# main.net
KiCad netlist of a schematic drawn in EAGLE
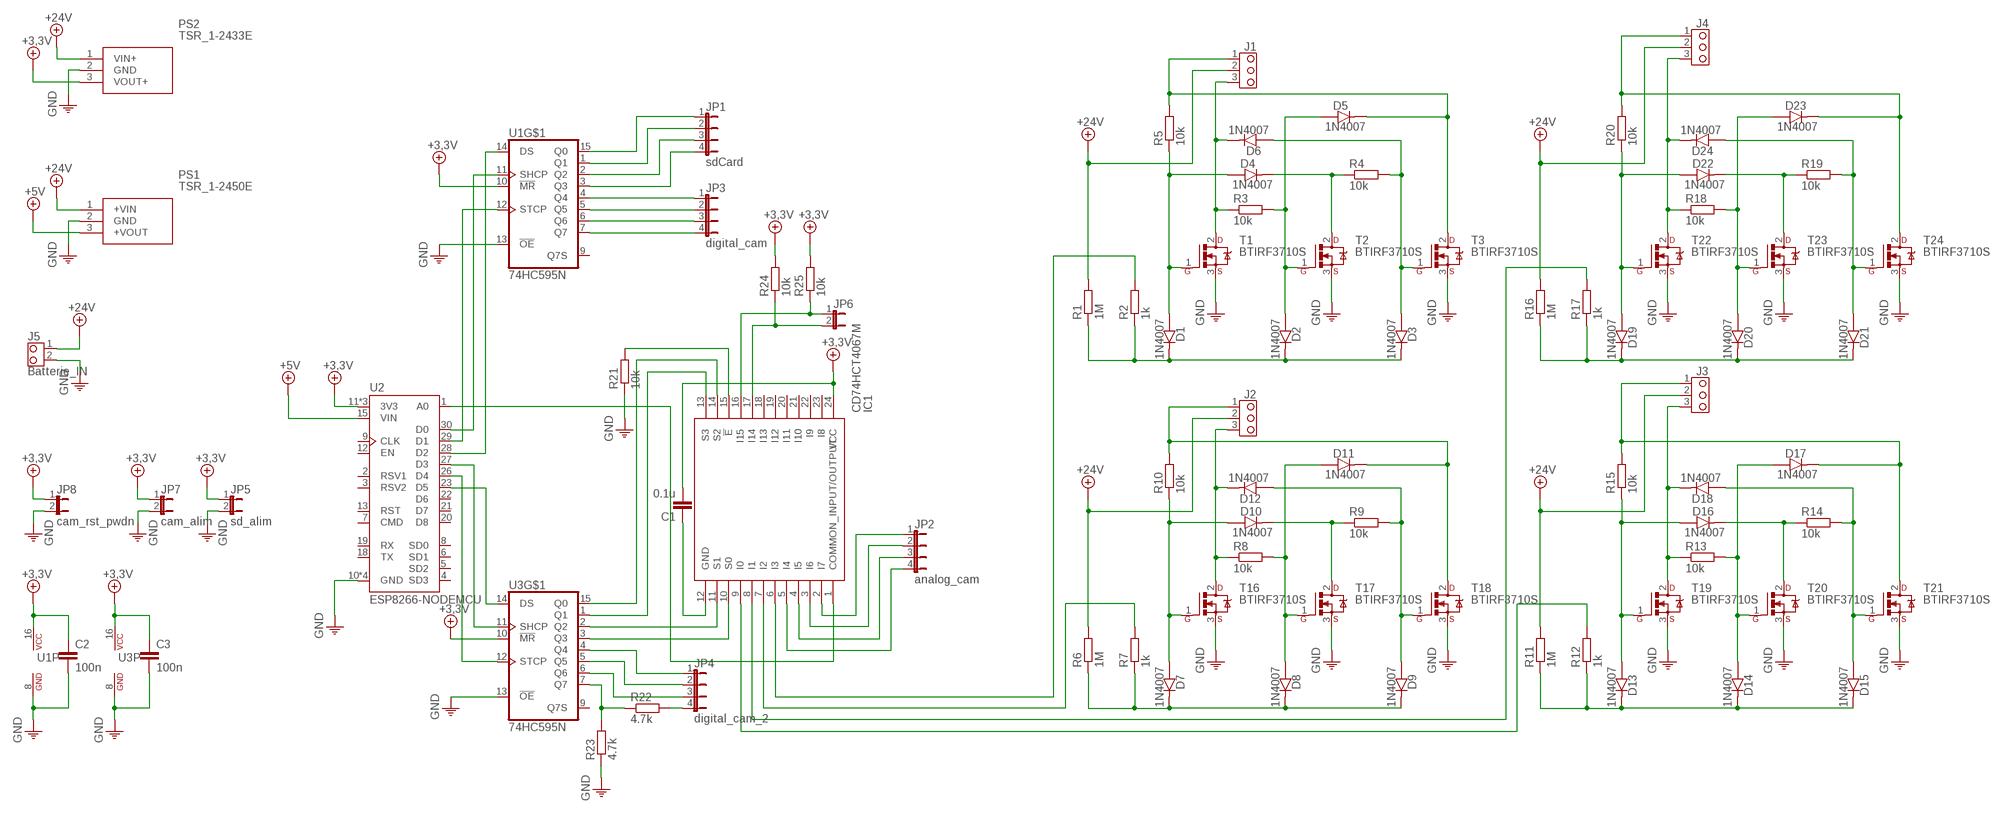
[diagram p0: schematic, sheet 1]

(export (version "E")
  (design (tool "Eeschema 10.0.6"))
  (components
    (comp (ref "C1")
      (value "0.1u")
      (footprint "eagle-import:CCMS1206")
      (libsource (lib "eagle-import") (part "C-CMS1206"))
    )
    (comp (ref "C2")
      (value "100n")
      (footprint "eagle-import:CCMS1206")
      (libsource (lib "eagle-import") (part "C-CMS1206"))
    )
    (comp (ref "C3")
      (value "100n")
      (footprint "eagle-import:CCMS1206")
      (libsource (lib "eagle-import") (part "C-CMS1206"))
    )
    (comp (ref "D1")
      (value "1N4007")
      (footprint "eagle-import:DO-41-10")
      (libsource (lib "eagle-import") (part "1N4007"))
    )
    (comp (ref "D2")
      (value "1N4007")
      (footprint "eagle-import:DO-41-10")
      (libsource (lib "eagle-import") (part "1N4007"))
    )
    (comp (ref "D3")
      (value "1N4007")
      (footprint "eagle-import:DO-41-10")
      (libsource (lib "eagle-import") (part "1N4007"))
    )
    (comp (ref "D4")
      (value "1N4007")
      (footprint "eagle-import:DO-41-10")
      (libsource (lib "eagle-import") (part "1N4007"))
    )
    (comp (ref "D5")
      (value "1N4007")
      (footprint "eagle-import:DO-41-10")
      (libsource (lib "eagle-import") (part "1N4007"))
    )
    (comp (ref "D6")
      (value "1N4007")
      (footprint "eagle-import:DO-41-10")
      (libsource (lib "eagle-import") (part "1N4007"))
    )
    (comp (ref "D7")
      (value "1N4007")
      (footprint "eagle-import:DO-41-10")
      (libsource (lib "eagle-import") (part "1N4007"))
    )
    (comp (ref "D8")
      (value "1N4007")
      (footprint "eagle-import:DO-41-10")
      (libsource (lib "eagle-import") (part "1N4007"))
    )
    (comp (ref "D9")
      (value "1N4007")
      (footprint "eagle-import:DO-41-10")
      (libsource (lib "eagle-import") (part "1N4007"))
    )
    (comp (ref "D10")
      (value "1N4007")
      (footprint "eagle-import:DO-41-10")
      (libsource (lib "eagle-import") (part "1N4007"))
    )
    (comp (ref "D11")
      (value "1N4007")
      (footprint "eagle-import:DO-41-10")
      (libsource (lib "eagle-import") (part "1N4007"))
    )
    (comp (ref "D12")
      (value "1N4007")
      (footprint "eagle-import:DO-41-10")
      (libsource (lib "eagle-import") (part "1N4007"))
    )
    (comp (ref "D13")
      (value "1N4007")
      (footprint "eagle-import:DO-41-10")
      (libsource (lib "eagle-import") (part "1N4007"))
    )
    (comp (ref "D14")
      (value "1N4007")
      (footprint "eagle-import:DO-41-10")
      (libsource (lib "eagle-import") (part "1N4007"))
    )
    (comp (ref "D15")
      (value "1N4007")
      (footprint "eagle-import:DO-41-10")
      (libsource (lib "eagle-import") (part "1N4007"))
    )
    (comp (ref "D16")
      (value "1N4007")
      (footprint "eagle-import:DO-41-10")
      (libsource (lib "eagle-import") (part "1N4007"))
    )
    (comp (ref "D17")
      (value "1N4007")
      (footprint "eagle-import:DO-41-10")
      (libsource (lib "eagle-import") (part "1N4007"))
    )
    (comp (ref "D18")
      (value "1N4007")
      (footprint "eagle-import:DO-41-10")
      (libsource (lib "eagle-import") (part "1N4007"))
    )
    (comp (ref "D19")
      (value "1N4007")
      (footprint "eagle-import:DO-41-10")
      (libsource (lib "eagle-import") (part "1N4007"))
    )
    (comp (ref "D20")
      (value "1N4007")
      (footprint "eagle-import:DO-41-10")
      (libsource (lib "eagle-import") (part "1N4007"))
    )
    (comp (ref "D21")
      (value "1N4007")
      (footprint "eagle-import:DO-41-10")
      (libsource (lib "eagle-import") (part "1N4007"))
    )
    (comp (ref "D22")
      (value "1N4007")
      (footprint "eagle-import:DO-41-10")
      (libsource (lib "eagle-import") (part "1N4007"))
    )
    (comp (ref "D23")
      (value "1N4007")
      (footprint "eagle-import:DO-41-10")
      (libsource (lib "eagle-import") (part "1N4007"))
    )
    (comp (ref "D24")
      (value "1N4007")
      (footprint "eagle-import:DO-41-10")
      (libsource (lib "eagle-import") (part "1N4007"))
    )
    (comp (ref "IC1")
      (value "CD74HCT4067M")
      (footprint "eagle-import:SOIC127P1030X265-24N")
      (fields (field (name "MOUSER_PART_NUMBER") "595-CD74HCT4067M"))
      (libsource (lib "eagle-import") (part "CD74HCT4067M"))
    )
    (comp (ref "J1")
      (value "BORNIER_3-A3P")
      (footprint "eagle-import:AK500_3")
      (libsource (lib "eagle-import") (part "BORNIER_3-A3P"))
    )
    (comp (ref "J2")
      (value "BORNIER_3-A3P")
      (footprint "eagle-import:AK500_3")
      (libsource (lib "eagle-import") (part "BORNIER_3-A3P"))
    )
    (comp (ref "J3")
      (value "BORNIER_3-A3P")
      (footprint "eagle-import:AK500_3")
      (libsource (lib "eagle-import") (part "BORNIER_3-A3P"))
    )
    (comp (ref "J4")
      (value "BORNIER_3-A3P")
      (footprint "eagle-import:AK500_3")
      (libsource (lib "eagle-import") (part "BORNIER_3-A3P"))
    )
    (comp (ref "J5")
      (value "Batterie_IN")
      (footprint "eagle-import:MSTBA2")
      (libsource (lib "eagle-import") (part "BORNIER_2-D2P"))
    )
    (comp (ref "JP1")
      (value "sdCard")
      (footprint "eagle-import:JP4")
      (libsource (lib "eagle-import") (part "JP4E"))
    )
    (comp (ref "JP2")
      (value "analog_cam")
      (footprint "eagle-import:JP4")
      (libsource (lib "eagle-import") (part "JP4E"))
    )
    (comp (ref "JP3")
      (value "digital_cam")
      (footprint "eagle-import:JP4")
      (libsource (lib "eagle-import") (part "JP4E"))
    )
    (comp (ref "JP4")
      (value "digital_cam_2")
      (footprint "eagle-import:JP4")
      (libsource (lib "eagle-import") (part "JP4E"))
    )
    (comp (ref "JP5")
      (value "sd_alim")
      (footprint "eagle-import:JP1")
      (libsource (lib "eagle-import") (part "JP1E"))
    )
    (comp (ref "JP6")
      (value "JP1E")
      (footprint "eagle-import:JP1")
      (libsource (lib "eagle-import") (part "JP1E"))
    )
    (comp (ref "JP7")
      (value "cam_alim")
      (footprint "eagle-import:JP1")
      (libsource (lib "eagle-import") (part "JP1E"))
    )
    (comp (ref "JP8")
      (value "cam_rst_pwdn")
      (footprint "eagle-import:JP1")
      (libsource (lib "eagle-import") (part "JP1E"))
    )
    (comp (ref "PS1")
      (value "TSR_1-2450E")
      (footprint "eagle-import:TSR12450E")
      (fields
        (field (name "MANUFACTURER_PART_NUMBER") "TSR 1-2450E")
        (field (name "MOUSER_PART_NUMBER") "495-TSR1-2450E")
      )
      (libsource (lib "eagle-import") (part "TSR_1-2450E"))
    )
    (comp (ref "PS2")
      (value "TSR_1-2433E")
      (footprint "eagle-import:TSR-1-2433")
      (fields
        (field (name "MANUFACTURER_PART_NUMBER") "TSR 1-2433E")
        (field (name "MOUSER_PART_NUMBER") "495-TSR1-2433E")
      )
      (libsource (lib "eagle-import") (part "TSR_1-2433E"))
    )
    (comp (ref "R1")
      (value "1M")
      (footprint "eagle-import:RCMS1206")
      (libsource (lib "eagle-import") (part "R-CMS1206"))
    )
    (comp (ref "R2")
      (value "1k")
      (footprint "eagle-import:RCMS1206")
      (libsource (lib "eagle-import") (part "R-CMS1206"))
    )
    (comp (ref "R3")
      (value "10k")
      (footprint "eagle-import:RCMS1206")
      (libsource (lib "eagle-import") (part "R-CMS1206"))
    )
    (comp (ref "R4")
      (value "10k")
      (footprint "eagle-import:RCMS1206")
      (libsource (lib "eagle-import") (part "R-CMS1206"))
    )
    (comp (ref "R5")
      (value "10k")
      (footprint "eagle-import:RCMS1206")
      (libsource (lib "eagle-import") (part "R-CMS1206"))
    )
    (comp (ref "R6")
      (value "1M")
      (footprint "eagle-import:RCMS1206")
      (libsource (lib "eagle-import") (part "R-CMS1206"))
    )
    (comp (ref "R7")
      (value "1k")
      (footprint "eagle-import:RCMS1206")
      (libsource (lib "eagle-import") (part "R-CMS1206"))
    )
    (comp (ref "R8")
      (value "10k")
      (footprint "eagle-import:RCMS1206")
      (libsource (lib "eagle-import") (part "R-CMS1206"))
    )
    (comp (ref "R9")
      (value "10k")
      (footprint "eagle-import:RCMS1206")
      (libsource (lib "eagle-import") (part "R-CMS1206"))
    )
    (comp (ref "R10")
      (value "10k")
      (footprint "eagle-import:RCMS1206")
      (libsource (lib "eagle-import") (part "R-CMS1206"))
    )
    (comp (ref "R11")
      (value "1M")
      (footprint "eagle-import:RCMS1206")
      (libsource (lib "eagle-import") (part "R-CMS1206"))
    )
    (comp (ref "R12")
      (value "1k")
      (footprint "eagle-import:RCMS1206")
      (libsource (lib "eagle-import") (part "R-CMS1206"))
    )
    (comp (ref "R13")
      (value "10k")
      (footprint "eagle-import:RCMS1206")
      (libsource (lib "eagle-import") (part "R-CMS1206"))
    )
    (comp (ref "R14")
      (value "10k")
      (footprint "eagle-import:RCMS1206")
      (libsource (lib "eagle-import") (part "R-CMS1206"))
    )
    (comp (ref "R15")
      (value "10k")
      (footprint "eagle-import:RCMS1206")
      (libsource (lib "eagle-import") (part "R-CMS1206"))
    )
    (comp (ref "R16")
      (value "1M")
      (footprint "eagle-import:RCMS1206")
      (libsource (lib "eagle-import") (part "R-CMS1206"))
    )
    (comp (ref "R17")
      (value "1k")
      (footprint "eagle-import:RCMS1206")
      (libsource (lib "eagle-import") (part "R-CMS1206"))
    )
    (comp (ref "R18")
      (value "10k")
      (footprint "eagle-import:RCMS1206")
      (libsource (lib "eagle-import") (part "R-CMS1206"))
    )
    (comp (ref "R19")
      (value "10k")
      (footprint "eagle-import:RCMS1206")
      (libsource (lib "eagle-import") (part "R-CMS1206"))
    )
    (comp (ref "R20")
      (value "10k")
      (footprint "eagle-import:RCMS1206")
      (libsource (lib "eagle-import") (part "R-CMS1206"))
    )
    (comp (ref "R21")
      (value "10k")
      (footprint "eagle-import:RCMS1206")
      (libsource (lib "eagle-import") (part "R-CMS1206"))
    )
    (comp (ref "R22")
      (value "4.7k")
      (footprint "eagle-import:RCMS1206")
      (libsource (lib "eagle-import") (part "R-CMS1206"))
    )
    (comp (ref "R23")
      (value "4.7k")
      (footprint "eagle-import:RCMS1206")
      (libsource (lib "eagle-import") (part "R-CMS1206"))
    )
    (comp (ref "R24")
      (value "10k")
      (footprint "eagle-import:RCMS1206")
      (libsource (lib "eagle-import") (part "R-CMS1206"))
    )
    (comp (ref "R25")
      (value "10k")
      (footprint "eagle-import:RCMS1206")
      (libsource (lib "eagle-import") (part "R-CMS1206"))
    )
    (comp (ref "T1")
      (value "BTIRF3710S")
      (footprint "eagle-import:D2PACK")
      (libsource (lib "eagle-import") (part "BTIRF3710S"))
    )
    (comp (ref "T2")
      (value "BTIRF3710S")
      (footprint "eagle-import:D2PACK")
      (libsource (lib "eagle-import") (part "BTIRF3710S"))
    )
    (comp (ref "T3")
      (value "BTIRF3710S")
      (footprint "eagle-import:D2PACK")
      (libsource (lib "eagle-import") (part "BTIRF3710S"))
    )
    (comp (ref "T16")
      (value "BTIRF3710S")
      (footprint "eagle-import:D2PACK")
      (libsource (lib "eagle-import") (part "BTIRF3710S"))
    )
    (comp (ref "T17")
      (value "BTIRF3710S")
      (footprint "eagle-import:D2PACK")
      (libsource (lib "eagle-import") (part "BTIRF3710S"))
    )
    (comp (ref "T18")
      (value "BTIRF3710S")
      (footprint "eagle-import:D2PACK")
      (libsource (lib "eagle-import") (part "BTIRF3710S"))
    )
    (comp (ref "T19")
      (value "BTIRF3710S")
      (footprint "eagle-import:D2PACK")
      (libsource (lib "eagle-import") (part "BTIRF3710S"))
    )
    (comp (ref "T20")
      (value "BTIRF3710S")
      (footprint "eagle-import:D2PACK")
      (libsource (lib "eagle-import") (part "BTIRF3710S"))
    )
    (comp (ref "T21")
      (value "BTIRF3710S")
      (footprint "eagle-import:D2PACK")
      (libsource (lib "eagle-import") (part "BTIRF3710S"))
    )
    (comp (ref "T22")
      (value "BTIRF3710S")
      (footprint "eagle-import:D2PACK")
      (libsource (lib "eagle-import") (part "BTIRF3710S"))
    )
    (comp (ref "T23")
      (value "BTIRF3710S")
      (footprint "eagle-import:D2PACK")
      (libsource (lib "eagle-import") (part "BTIRF3710S"))
    )
    (comp (ref "T24")
      (value "BTIRF3710S")
      (footprint "eagle-import:D2PACK")
      (libsource (lib "eagle-import") (part "BTIRF3710S"))
    )
    (comp (ref "U1")
      (value "74HC595N")
      (footprint "eagle-import:DIL16")
      (libsource (lib "eagle-import") (part "74HC595N"))
    )
    (comp (ref "U2")
      (value "ESP8266-NODEMCU")
      (footprint "eagle-import:ESP8266-NODEMCU")
      (libsource (lib "eagle-import") (part "ESP8266-NODEMCU"))
    )
    (comp (ref "U3")
      (value "74HC595N")
      (footprint "eagle-import:DIL16")
      (libsource (lib "eagle-import") (part "74HC595N"))
    )
  )
  (nets
    (net (code "1") (name "+3,3V") (class "Default")
      (node (ref "C1") (pin "2") (pinfunction "2_2") (pintype "passive"))
      (node (ref "C2") (pin "1") (pinfunction "1_1") (pintype "passive"))
      (node (ref "C3") (pin "1") (pinfunction "1_1") (pintype "passive"))
      (node (ref "IC1") (pin "24") (pinfunction "VCC_24") (pintype "bidirectional"))
      (node (ref "JP5") (pin "1") (pinfunction "1_1") (pintype "passive"))
      (node (ref "JP7") (pin "1") (pinfunction "1_1") (pintype "passive"))
      (node (ref "JP8") (pin "1") (pinfunction "1_1") (pintype "passive"))
      (node (ref "PS2") (pin "3") (pinfunction "VOUT+_3") (pintype "output"))
      (node (ref "R24") (pin "2") (pinfunction "2_2") (pintype "passive"))
      (node (ref "R25") (pin "2") (pinfunction "2_2") (pintype "passive"))
      (node (ref "U1") (pin "10") (pinfunction "~{MR}_10") (pintype "input"))
      (node (ref "U1") (pin "16") (pinfunction "VCC_16") (pintype "power_in"))
      (node (ref "U2") (pin "11") (pinfunction "3V3_11") (pintype "power_in"))
      (node (ref "U2") (pin "16") (pinfunction "3V3_16") (pintype "power_in"))
      (node (ref "U2") (pin "25") (pinfunction "3V3_25") (pintype "power_in"))
      (node (ref "U3") (pin "10") (pinfunction "~{MR}_10") (pintype "input"))
      (node (ref "U3") (pin "16") (pinfunction "VCC_16") (pintype "power_in"))
    )
    (net (code "2") (name "+5V") (class "Default")
      (node (ref "PS1") (pin "3") (pinfunction "+VOUT_3") (pintype "bidirectional"))
      (node (ref "U2") (pin "15") (pinfunction "VIN_15") (pintype "power_in"))
    )
    (net (code "3") (name "+24V") (class "Default")
      (node (ref "J1") (pin "2") (pinfunction "2_2") (pintype "passive"))
      (node (ref "J2") (pin "2") (pinfunction "2_2") (pintype "passive"))
      (node (ref "J3") (pin "2") (pinfunction "2_2") (pintype "passive"))
      (node (ref "J4") (pin "2") (pinfunction "2_2") (pintype "passive"))
      (node (ref "J5") (pin "1") (pinfunction "1_1") (pintype "passive"))
      (node (ref "PS1") (pin "1") (pinfunction "+VIN_1") (pintype "bidirectional"))
      (node (ref "PS2") (pin "1") (pinfunction "VIN+_1") (pintype "input"))
      (node (ref "R1") (pin "2") (pinfunction "2_2") (pintype "passive"))
      (node (ref "R11") (pin "2") (pinfunction "2_2") (pintype "passive"))
      (node (ref "R16") (pin "2") (pinfunction "2_2") (pintype "passive"))
      (node (ref "R6") (pin "2") (pinfunction "2_2") (pintype "passive"))
    )
    (net (code "4") (name "GND") (class "Default")
      (node (ref "C2") (pin "2") (pinfunction "2_2") (pintype "passive"))
      (node (ref "C3") (pin "2") (pinfunction "2_2") (pintype "passive"))
      (node (ref "J5") (pin "2") (pinfunction "2_2") (pintype "passive"))
      (node (ref "JP5") (pin "2") (pinfunction "2_2") (pintype "passive"))
      (node (ref "JP7") (pin "2") (pinfunction "2_2") (pintype "passive"))
      (node (ref "JP8") (pin "2") (pinfunction "2_2") (pintype "passive"))
      (node (ref "PS1") (pin "2") (pinfunction "GND_2") (pintype "bidirectional"))
      (node (ref "PS2") (pin "2") (pinfunction "GND_2") (pintype "power_in"))
      (node (ref "R21") (pin "1") (pinfunction "1_1") (pintype "passive"))
      (node (ref "R23") (pin "1") (pinfunction "1_1") (pintype "passive"))
      (node (ref "T1") (pin "3") (pinfunction "S_3") (pintype "passive"))
      (node (ref "T16") (pin "3") (pinfunction "S_3") (pintype "passive"))
      (node (ref "T17") (pin "3") (pinfunction "S_3") (pintype "passive"))
      (node (ref "T18") (pin "3") (pinfunction "S_3") (pintype "passive"))
      (node (ref "T19") (pin "3") (pinfunction "S_3") (pintype "passive"))
      (node (ref "T2") (pin "3") (pinfunction "S_3") (pintype "passive"))
      (node (ref "T20") (pin "3") (pinfunction "S_3") (pintype "passive"))
      (node (ref "T21") (pin "3") (pinfunction "S_3") (pintype "passive"))
      (node (ref "T22") (pin "3") (pinfunction "S_3") (pintype "passive"))
      (node (ref "T23") (pin "3") (pinfunction "S_3") (pintype "passive"))
      (node (ref "T24") (pin "3") (pinfunction "S_3") (pintype "passive"))
      (node (ref "T3") (pin "3") (pinfunction "S_3") (pintype "passive"))
      (node (ref "U1") (pin "13") (pinfunction "~{OE}_13") (pintype "input"))
      (node (ref "U1") (pin "8") (pinfunction "GND_8") (pintype "power_in"))
      (node (ref "U2") (pin "10") (pinfunction "GND_10") (pintype "power_in"))
      (node (ref "U2") (pin "14") (pinfunction "GND_14") (pintype "power_in"))
      (node (ref "U2") (pin "17") (pinfunction "GND_17") (pintype "power_in"))
      (node (ref "U2") (pin "24") (pinfunction "GND_24") (pintype "power_in"))
      (node (ref "U3") (pin "13") (pinfunction "~{OE}_13") (pintype "input"))
      (node (ref "U3") (pin "8") (pinfunction "GND_8") (pintype "power_in"))
    )
    (net (code "5") (name "Net-(D1-PadC)") (class "Default")
      (node (ref "D1") (pin "C") (pinfunction "C_C") (pintype "passive"))
      (node (ref "D2") (pin "C") (pinfunction "C_C") (pintype "passive"))
      (node (ref "D3") (pin "C") (pinfunction "C_C") (pintype "passive"))
      (node (ref "R1") (pin "1") (pinfunction "1_1") (pintype "passive"))
      (node (ref "R2") (pin "1") (pinfunction "1_1") (pintype "passive"))
    )
    (net (code "6") (name "Net-(D7-PadC)") (class "Default")
      (node (ref "D7") (pin "C") (pinfunction "C_C") (pintype "passive"))
      (node (ref "D8") (pin "C") (pinfunction "C_C") (pintype "passive"))
      (node (ref "D9") (pin "C") (pinfunction "C_C") (pintype "passive"))
      (node (ref "R6") (pin "1") (pinfunction "1_1") (pintype "passive"))
      (node (ref "R7") (pin "1") (pinfunction "1_1") (pintype "passive"))
    )
    (net (code "7") (name "Net-(D13-PadC)") (class "Default")
      (node (ref "D13") (pin "C") (pinfunction "C_C") (pintype "passive"))
      (node (ref "D14") (pin "C") (pinfunction "C_C") (pintype "passive"))
      (node (ref "D15") (pin "C") (pinfunction "C_C") (pintype "passive"))
      (node (ref "R11") (pin "1") (pinfunction "1_1") (pintype "passive"))
      (node (ref "R12") (pin "1") (pinfunction "1_1") (pintype "passive"))
    )
    (net (code "8") (name "Net-(D19-PadC)") (class "Default")
      (node (ref "D19") (pin "C") (pinfunction "C_C") (pintype "passive"))
      (node (ref "D20") (pin "C") (pinfunction "C_C") (pintype "passive"))
      (node (ref "D21") (pin "C") (pinfunction "C_C") (pintype "passive"))
      (node (ref "R16") (pin "1") (pinfunction "1_1") (pintype "passive"))
      (node (ref "R17") (pin "1") (pinfunction "1_1") (pintype "passive"))
    )
    (net (code "9") (name "Net-(IC1-COMMON_INPUT{slash}OUTPUT)") (class "Default")
      (node (ref "IC1") (pin "1") (pinfunction "COMMON_INPUT/OUTPUT_1") (pintype "bidirectional"))
      (node (ref "U2") (pin "1") (pinfunction "A0_1") (pintype "bidirectional"))
    )
    (net (code "10") (name "Net-(IC1-GND)") (class "Default")
      (node (ref "C1") (pin "1") (pinfunction "1_1") (pintype "passive"))
      (node (ref "IC1") (pin "12") (pinfunction "GND_12") (pintype "bidirectional"))
    )
    (net (code "11") (name "Net-(IC1-I0)") (class "Default")
      (node (ref "IC1") (pin "9") (pinfunction "I0_9") (pintype "bidirectional"))
      (node (ref "R12") (pin "2") (pinfunction "2_2") (pintype "passive"))
    )
    (net (code "12") (name "Net-(IC1-I1)") (class "Default")
      (node (ref "IC1") (pin "8") (pinfunction "I1_8") (pintype "bidirectional"))
      (node (ref "R17") (pin "2") (pinfunction "2_2") (pintype "passive"))
    )
    (net (code "13") (name "Net-(IC1-I2)") (class "Default")
      (node (ref "IC1") (pin "7") (pinfunction "I2_7") (pintype "bidirectional"))
      (node (ref "R7") (pin "2") (pinfunction "2_2") (pintype "passive"))
    )
    (net (code "14") (name "Net-(IC1-I3)") (class "Default")
      (node (ref "IC1") (pin "6") (pinfunction "I3_6") (pintype "bidirectional"))
      (node (ref "R2") (pin "2") (pinfunction "2_2") (pintype "passive"))
    )
    (net (code "15") (name "Net-(IC1-I4)") (class "Default")
      (node (ref "IC1") (pin "5") (pinfunction "I4_5") (pintype "bidirectional"))
      (node (ref "JP2") (pin "4") (pinfunction "4_4") (pintype "passive"))
    )
    (net (code "16") (name "Net-(IC1-I5)") (class "Default")
      (node (ref "IC1") (pin "4") (pinfunction "I5_4") (pintype "bidirectional"))
      (node (ref "JP2") (pin "3") (pinfunction "3_3") (pintype "passive"))
    )
    (net (code "17") (name "Net-(IC1-I6)") (class "Default")
      (node (ref "IC1") (pin "3") (pinfunction "I6_3") (pintype "bidirectional"))
      (node (ref "JP2") (pin "2") (pinfunction "2_2") (pintype "passive"))
    )
    (net (code "18") (name "Net-(IC1-I7)") (class "Default")
      (node (ref "IC1") (pin "2") (pinfunction "I7_2") (pintype "bidirectional"))
      (node (ref "JP2") (pin "1") (pinfunction "1_1") (pintype "passive"))
    )
    (net (code "19") (name "Net-(IC1-I14)") (class "Default")
      (node (ref "IC1") (pin "17") (pinfunction "I14_17") (pintype "bidirectional"))
      (node (ref "JP6") (pin "2") (pinfunction "2_2") (pintype "passive"))
      (node (ref "R24") (pin "1") (pinfunction "1_1") (pintype "passive"))
    )
    (net (code "20") (name "Net-(IC1-I15)") (class "Default")
      (node (ref "IC1") (pin "16") (pinfunction "I15_16") (pintype "bidirectional"))
      (node (ref "JP6") (pin "1") (pinfunction "1_1") (pintype "passive"))
      (node (ref "R25") (pin "1") (pinfunction "1_1") (pintype "passive"))
    )
    (net (code "21") (name "Net-(IC1-S0)") (class "Default")
      (node (ref "IC1") (pin "10") (pinfunction "S0_10") (pintype "bidirectional"))
      (node (ref "U3") (pin "3") (pinfunction "Q3_3") (pintype "tri_state"))
    )
    (net (code "22") (name "Net-(IC1-S1)") (class "Default")
      (node (ref "IC1") (pin "11") (pinfunction "S1_11") (pintype "bidirectional"))
      (node (ref "U3") (pin "2") (pinfunction "Q2_2") (pintype "tri_state"))
    )
    (net (code "23") (name "Net-(IC1-S2)") (class "Default")
      (node (ref "IC1") (pin "14") (pinfunction "S2_14") (pintype "bidirectional"))
      (node (ref "U3") (pin "15") (pinfunction "Q0_15") (pintype "tri_state"))
    )
    (net (code "24") (name "Net-(IC1-S3)") (class "Default")
      (node (ref "IC1") (pin "13") (pinfunction "S3_13") (pintype "bidirectional"))
      (node (ref "U3") (pin "1") (pinfunction "Q1_1") (pintype "tri_state"))
    )
    (net (code "25") (name "Net-(IC1-~{E})") (class "Default")
      (node (ref "IC1") (pin "15") (pinfunction "~{E}_15") (pintype "bidirectional"))
      (node (ref "R21") (pin "2") (pinfunction "2_2") (pintype "passive"))
    )
    (net (code "26") (name "Net-(JP4-Pad4)") (class "Default")
      (node (ref "JP4") (pin "4") (pinfunction "4_4") (pintype "passive"))
      (node (ref "R22") (pin "2") (pinfunction "2_2") (pintype "passive"))
    )
    (net (code "27") (name "Net-(T1-D)") (class "Default")
      (node (ref "D6") (pin "C") (pinfunction "C_C") (pintype "passive"))
      (node (ref "J1") (pin "3") (pinfunction "3_3") (pintype "passive"))
      (node (ref "R3") (pin "1") (pinfunction "1_1") (pintype "passive"))
      (node (ref "T1") (pin "2") (pinfunction "D_2") (pintype "passive"))
    )
    (net (code "28") (name "Net-(T1-G)") (class "Default")
      (node (ref "D1") (pin "A") (pinfunction "A_A") (pintype "passive"))
      (node (ref "D4") (pin "A") (pinfunction "A_A") (pintype "passive"))
      (node (ref "R5") (pin "1") (pinfunction "1_1") (pintype "passive"))
      (node (ref "T1") (pin "1") (pinfunction "G_1") (pintype "passive"))
    )
    (net (code "29") (name "Net-(T2-D)") (class "Default")
      (node (ref "D4") (pin "C") (pinfunction "C_C") (pintype "passive"))
      (node (ref "R4") (pin "1") (pinfunction "1_1") (pintype "passive"))
      (node (ref "T2") (pin "2") (pinfunction "D_2") (pintype "passive"))
    )
    (net (code "30") (name "Net-(T2-G)") (class "Default")
      (node (ref "D2") (pin "A") (pinfunction "A_A") (pintype "passive"))
      (node (ref "D5") (pin "A") (pinfunction "A_A") (pintype "passive"))
      (node (ref "R3") (pin "2") (pinfunction "2_2") (pintype "passive"))
      (node (ref "T2") (pin "1") (pinfunction "G_1") (pintype "passive"))
    )
    (net (code "31") (name "Net-(T3-D)") (class "Default")
      (node (ref "D5") (pin "C") (pinfunction "C_C") (pintype "passive"))
      (node (ref "J1") (pin "1") (pinfunction "1_1") (pintype "passive"))
      (node (ref "R5") (pin "2") (pinfunction "2_2") (pintype "passive"))
      (node (ref "T3") (pin "2") (pinfunction "D_2") (pintype "passive"))
    )
    (net (code "32") (name "Net-(T3-G)") (class "Default")
      (node (ref "D3") (pin "A") (pinfunction "A_A") (pintype "passive"))
      (node (ref "D6") (pin "A") (pinfunction "A_A") (pintype "passive"))
      (node (ref "R4") (pin "2") (pinfunction "2_2") (pintype "passive"))
      (node (ref "T3") (pin "1") (pinfunction "G_1") (pintype "passive"))
    )
    (net (code "33") (name "Net-(T16-D)") (class "Default")
      (node (ref "D12") (pin "C") (pinfunction "C_C") (pintype "passive"))
      (node (ref "J2") (pin "3") (pinfunction "3_3") (pintype "passive"))
      (node (ref "R8") (pin "1") (pinfunction "1_1") (pintype "passive"))
      (node (ref "T16") (pin "2") (pinfunction "D_2") (pintype "passive"))
    )
    (net (code "34") (name "Net-(T16-G)") (class "Default")
      (node (ref "D10") (pin "A") (pinfunction "A_A") (pintype "passive"))
      (node (ref "D7") (pin "A") (pinfunction "A_A") (pintype "passive"))
      (node (ref "R10") (pin "1") (pinfunction "1_1") (pintype "passive"))
      (node (ref "T16") (pin "1") (pinfunction "G_1") (pintype "passive"))
    )
    (net (code "35") (name "Net-(T17-D)") (class "Default")
      (node (ref "D10") (pin "C") (pinfunction "C_C") (pintype "passive"))
      (node (ref "R9") (pin "1") (pinfunction "1_1") (pintype "passive"))
      (node (ref "T17") (pin "2") (pinfunction "D_2") (pintype "passive"))
    )
    (net (code "36") (name "Net-(T17-G)") (class "Default")
      (node (ref "D11") (pin "A") (pinfunction "A_A") (pintype "passive"))
      (node (ref "D8") (pin "A") (pinfunction "A_A") (pintype "passive"))
      (node (ref "R8") (pin "2") (pinfunction "2_2") (pintype "passive"))
      (node (ref "T17") (pin "1") (pinfunction "G_1") (pintype "passive"))
    )
    (net (code "37") (name "Net-(T18-D)") (class "Default")
      (node (ref "D11") (pin "C") (pinfunction "C_C") (pintype "passive"))
      (node (ref "J2") (pin "1") (pinfunction "1_1") (pintype "passive"))
      (node (ref "R10") (pin "2") (pinfunction "2_2") (pintype "passive"))
      (node (ref "T18") (pin "2") (pinfunction "D_2") (pintype "passive"))
    )
    (net (code "38") (name "Net-(T18-G)") (class "Default")
      (node (ref "D12") (pin "A") (pinfunction "A_A") (pintype "passive"))
      (node (ref "D9") (pin "A") (pinfunction "A_A") (pintype "passive"))
      (node (ref "R9") (pin "2") (pinfunction "2_2") (pintype "passive"))
      (node (ref "T18") (pin "1") (pinfunction "G_1") (pintype "passive"))
    )
    (net (code "39") (name "Net-(T19-D)") (class "Default")
      (node (ref "D18") (pin "C") (pinfunction "C_C") (pintype "passive"))
      (node (ref "J3") (pin "3") (pinfunction "3_3") (pintype "passive"))
      (node (ref "R13") (pin "1") (pinfunction "1_1") (pintype "passive"))
      (node (ref "T19") (pin "2") (pinfunction "D_2") (pintype "passive"))
    )
    (net (code "40") (name "Net-(T19-G)") (class "Default")
      (node (ref "D13") (pin "A") (pinfunction "A_A") (pintype "passive"))
      (node (ref "D16") (pin "A") (pinfunction "A_A") (pintype "passive"))
      (node (ref "R15") (pin "1") (pinfunction "1_1") (pintype "passive"))
      (node (ref "T19") (pin "1") (pinfunction "G_1") (pintype "passive"))
    )
    (net (code "41") (name "Net-(T20-D)") (class "Default")
      (node (ref "D16") (pin "C") (pinfunction "C_C") (pintype "passive"))
      (node (ref "R14") (pin "1") (pinfunction "1_1") (pintype "passive"))
      (node (ref "T20") (pin "2") (pinfunction "D_2") (pintype "passive"))
    )
    (net (code "42") (name "Net-(T20-G)") (class "Default")
      (node (ref "D14") (pin "A") (pinfunction "A_A") (pintype "passive"))
      (node (ref "D17") (pin "A") (pinfunction "A_A") (pintype "passive"))
      (node (ref "R13") (pin "2") (pinfunction "2_2") (pintype "passive"))
      (node (ref "T20") (pin "1") (pinfunction "G_1") (pintype "passive"))
    )
    (net (code "43") (name "Net-(T21-D)") (class "Default")
      (node (ref "D17") (pin "C") (pinfunction "C_C") (pintype "passive"))
      (node (ref "J3") (pin "1") (pinfunction "1_1") (pintype "passive"))
      (node (ref "R15") (pin "2") (pinfunction "2_2") (pintype "passive"))
      (node (ref "T21") (pin "2") (pinfunction "D_2") (pintype "passive"))
    )
    (net (code "44") (name "Net-(T21-G)") (class "Default")
      (node (ref "D15") (pin "A") (pinfunction "A_A") (pintype "passive"))
      (node (ref "D18") (pin "A") (pinfunction "A_A") (pintype "passive"))
      (node (ref "R14") (pin "2") (pinfunction "2_2") (pintype "passive"))
      (node (ref "T21") (pin "1") (pinfunction "G_1") (pintype "passive"))
    )
    (net (code "45") (name "Net-(T22-D)") (class "Default")
      (node (ref "D24") (pin "C") (pinfunction "C_C") (pintype "passive"))
      (node (ref "J4") (pin "3") (pinfunction "3_3") (pintype "passive"))
      (node (ref "R18") (pin "1") (pinfunction "1_1") (pintype "passive"))
      (node (ref "T22") (pin "2") (pinfunction "D_2") (pintype "passive"))
    )
    (net (code "46") (name "Net-(T22-G)") (class "Default")
      (node (ref "D19") (pin "A") (pinfunction "A_A") (pintype "passive"))
      (node (ref "D22") (pin "A") (pinfunction "A_A") (pintype "passive"))
      (node (ref "R20") (pin "1") (pinfunction "1_1") (pintype "passive"))
      (node (ref "T22") (pin "1") (pinfunction "G_1") (pintype "passive"))
    )
    (net (code "47") (name "Net-(T23-D)") (class "Default")
      (node (ref "D22") (pin "C") (pinfunction "C_C") (pintype "passive"))
      (node (ref "R19") (pin "1") (pinfunction "1_1") (pintype "passive"))
      (node (ref "T23") (pin "2") (pinfunction "D_2") (pintype "passive"))
    )
    (net (code "48") (name "Net-(T23-G)") (class "Default")
      (node (ref "D20") (pin "A") (pinfunction "A_A") (pintype "passive"))
      (node (ref "D23") (pin "A") (pinfunction "A_A") (pintype "passive"))
      (node (ref "R18") (pin "2") (pinfunction "2_2") (pintype "passive"))
      (node (ref "T23") (pin "1") (pinfunction "G_1") (pintype "passive"))
    )
    (net (code "49") (name "Net-(T24-D)") (class "Default")
      (node (ref "D23") (pin "C") (pinfunction "C_C") (pintype "passive"))
      (node (ref "J4") (pin "1") (pinfunction "1_1") (pintype "passive"))
      (node (ref "R20") (pin "2") (pinfunction "2_2") (pintype "passive"))
      (node (ref "T24") (pin "2") (pinfunction "D_2") (pintype "passive"))
    )
    (net (code "50") (name "Net-(T24-G)") (class "Default")
      (node (ref "D21") (pin "A") (pinfunction "A_A") (pintype "passive"))
      (node (ref "D24") (pin "A") (pinfunction "A_A") (pintype "passive"))
      (node (ref "R19") (pin "2") (pinfunction "2_2") (pintype "passive"))
      (node (ref "T24") (pin "1") (pinfunction "G_1") (pintype "passive"))
    )
    (net (code "51") (name "Net-(U1A-DS)") (class "Default")
      (node (ref "U1") (pin "14") (pinfunction "DS_14") (pintype "input"))
      (node (ref "U2") (pin "28") (pinfunction "D2_28") (pintype "bidirectional"))
    )
    (net (code "52") (name "Net-(U1A-Q0)") (class "Default")
      (node (ref "JP1") (pin "1") (pinfunction "1_1") (pintype "passive"))
      (node (ref "U1") (pin "15") (pinfunction "Q0_15") (pintype "tri_state"))
    )
    (net (code "53") (name "Net-(U1A-Q1)") (class "Default")
      (node (ref "JP1") (pin "2") (pinfunction "2_2") (pintype "passive"))
      (node (ref "U1") (pin "1") (pinfunction "Q1_1") (pintype "tri_state"))
    )
    (net (code "54") (name "Net-(U1A-Q2)") (class "Default")
      (node (ref "JP1") (pin "3") (pinfunction "3_3") (pintype "passive"))
      (node (ref "U1") (pin "2") (pinfunction "Q2_2") (pintype "tri_state"))
    )
    (net (code "55") (name "Net-(U1A-Q3)") (class "Default")
      (node (ref "JP1") (pin "4") (pinfunction "4_4") (pintype "passive"))
      (node (ref "U1") (pin "3") (pinfunction "Q3_3") (pintype "tri_state"))
    )
    (net (code "56") (name "Net-(U1A-Q4)") (class "Default")
      (node (ref "JP3") (pin "1") (pinfunction "1_1") (pintype "passive"))
      (node (ref "U1") (pin "4") (pinfunction "Q4_4") (pintype "tri_state"))
    )
    (net (code "57") (name "Net-(U1A-Q5)") (class "Default")
      (node (ref "JP3") (pin "2") (pinfunction "2_2") (pintype "passive"))
      (node (ref "U1") (pin "5") (pinfunction "Q5_5") (pintype "tri_state"))
    )
    (net (code "58") (name "Net-(U1A-Q6)") (class "Default")
      (node (ref "JP3") (pin "3") (pinfunction "3_3") (pintype "passive"))
      (node (ref "U1") (pin "6") (pinfunction "Q6_6") (pintype "tri_state"))
    )
    (net (code "59") (name "Net-(U1A-Q7)") (class "Default")
      (node (ref "JP3") (pin "4") (pinfunction "4_4") (pintype "passive"))
      (node (ref "U1") (pin "7") (pinfunction "Q7_7") (pintype "tri_state"))
    )
    (net (code "60") (name "Net-(U1A-SHCP)") (class "Default")
      (node (ref "U1") (pin "11") (pinfunction "SHCP_11") (pintype "input"))
      (node (ref "U2") (pin "30") (pinfunction "D0_30") (pintype "bidirectional"))
    )
    (net (code "61") (name "Net-(U1A-STCP)") (class "Default")
      (node (ref "U1") (pin "12") (pinfunction "STCP_12") (pintype "input"))
      (node (ref "U2") (pin "29") (pinfunction "D1_29") (pintype "bidirectional"))
    )
    (net (code "62") (name "Net-(U2-D3)") (class "Default")
      (node (ref "U2") (pin "27") (pinfunction "D3_27") (pintype "bidirectional"))
      (node (ref "U3") (pin "11") (pinfunction "SHCP_11") (pintype "input"))
    )
    (net (code "63") (name "Net-(U2-D4)") (class "Default")
      (node (ref "U2") (pin "26") (pinfunction "D4_26") (pintype "bidirectional"))
      (node (ref "U3") (pin "12") (pinfunction "STCP_12") (pintype "input"))
    )
    (net (code "64") (name "Net-(U2-D5)") (class "Default")
      (node (ref "U2") (pin "23") (pinfunction "D5_23") (pintype "bidirectional"))
      (node (ref "U3") (pin "14") (pinfunction "DS_14") (pintype "input"))
    )
    (net (code "65") (name "Net-(U3A-Q4)") (class "Default")
      (node (ref "JP4") (pin "1") (pinfunction "1_1") (pintype "passive"))
      (node (ref "U3") (pin "4") (pinfunction "Q4_4") (pintype "tri_state"))
    )
    (net (code "66") (name "Net-(U3A-Q5)") (class "Default")
      (node (ref "JP4") (pin "2") (pinfunction "2_2") (pintype "passive"))
      (node (ref "U3") (pin "5") (pinfunction "Q5_5") (pintype "tri_state"))
    )
    (net (code "67") (name "Net-(U3A-Q6)") (class "Default")
      (node (ref "JP4") (pin "3") (pinfunction "3_3") (pintype "passive"))
      (node (ref "U3") (pin "6") (pinfunction "Q6_6") (pintype "tri_state"))
    )
    (net (code "68") (name "Net-(U3A-Q7)") (class "Default")
      (node (ref "R22") (pin "1") (pinfunction "1_1") (pintype "passive"))
      (node (ref "R23") (pin "2") (pinfunction "2_2") (pintype "passive"))
      (node (ref "U3") (pin "7") (pinfunction "Q7_7") (pintype "tri_state"))
    )
    (net (code "69") (name "unconnected-(IC1-I8-Pad23)") (class "Default")
      (node (ref "IC1") (pin "23") (pinfunction "I8_23") (pintype "bidirectional"))
    )
    (net (code "70") (name "unconnected-(IC1-I9-Pad22)") (class "Default")
      (node (ref "IC1") (pin "22") (pinfunction "I9_22") (pintype "bidirectional"))
    )
    (net (code "71") (name "unconnected-(IC1-I10-Pad21)") (class "Default")
      (node (ref "IC1") (pin "21") (pinfunction "I10_21") (pintype "bidirectional"))
    )
    (net (code "72") (name "unconnected-(IC1-I11-Pad20)") (class "Default")
      (node (ref "IC1") (pin "20") (pinfunction "I11_20") (pintype "bidirectional"))
    )
    (net (code "73") (name "unconnected-(IC1-I12-Pad19)") (class "Default")
      (node (ref "IC1") (pin "19") (pinfunction "I12_19") (pintype "bidirectional"))
    )
    (net (code "74") (name "unconnected-(IC1-I13-Pad18)") (class "Default")
      (node (ref "IC1") (pin "18") (pinfunction "I13_18") (pintype "bidirectional"))
    )
    (net (code "75") (name "unconnected-(U1A-Q7S-Pad9)") (class "Default")
      (node (ref "U1") (pin "9") (pinfunction "Q7S_9") (pintype "tri_state"))
    )
    (net (code "76") (name "unconnected-(U2-CLK-Pad9)") (class "Default")
      (node (ref "U2") (pin "9") (pinfunction "CLK_9") (pintype "bidirectional"))
    )
    (net (code "77") (name "unconnected-(U2-CMD-Pad7)") (class "Default")
      (node (ref "U2") (pin "7") (pinfunction "CMD_7") (pintype "bidirectional"))
    )
    (net (code "78") (name "unconnected-(U2-D6-Pad22)") (class "Default")
      (node (ref "U2") (pin "22") (pinfunction "D6_22") (pintype "bidirectional"))
    )
    (net (code "79") (name "unconnected-(U2-D7-Pad21)") (class "Default")
      (node (ref "U2") (pin "21") (pinfunction "D7_21") (pintype "bidirectional"))
    )
    (net (code "80") (name "unconnected-(U2-D8-Pad20)") (class "Default")
      (node (ref "U2") (pin "20") (pinfunction "D8_20") (pintype "bidirectional"))
    )
    (net (code "81") (name "unconnected-(U2-EN-Pad12)") (class "Default")
      (node (ref "U2") (pin "12") (pinfunction "EN_12") (pintype "bidirectional"))
    )
    (net (code "82") (name "unconnected-(U2-RST-Pad13)") (class "Default")
      (node (ref "U2") (pin "13") (pinfunction "RST_13") (pintype "bidirectional"))
    )
    (net (code "83") (name "unconnected-(U2-RSV1-Pad2)") (class "Default")
      (node (ref "U2") (pin "2") (pinfunction "RSV1_2") (pintype "bidirectional"))
    )
    (net (code "84") (name "unconnected-(U2-RSV2-Pad3)") (class "Default")
      (node (ref "U2") (pin "3") (pinfunction "RSV2_3") (pintype "bidirectional"))
    )
    (net (code "85") (name "unconnected-(U2-RX-Pad19)") (class "Default")
      (node (ref "U2") (pin "19") (pinfunction "RX_19") (pintype "bidirectional"))
    )
    (net (code "86") (name "unconnected-(U2-SD0-Pad8)") (class "Default")
      (node (ref "U2") (pin "8") (pinfunction "SD0_8") (pintype "bidirectional"))
    )
    (net (code "87") (name "unconnected-(U2-SD1-Pad6)") (class "Default")
      (node (ref "U2") (pin "6") (pinfunction "SD1_6") (pintype "bidirectional"))
    )
    (net (code "88") (name "unconnected-(U2-SD2-Pad5)") (class "Default")
      (node (ref "U2") (pin "5") (pinfunction "SD2_5") (pintype "bidirectional"))
    )
    (net (code "89") (name "unconnected-(U2-SD3-Pad4)") (class "Default")
      (node (ref "U2") (pin "4") (pinfunction "SD3_4") (pintype "bidirectional"))
    )
    (net (code "90") (name "unconnected-(U2-TX-Pad18)") (class "Default")
      (node (ref "U2") (pin "18") (pinfunction "TX_18") (pintype "bidirectional"))
    )
    (net (code "91") (name "unconnected-(U3A-Q7S-Pad9)") (class "Default")
      (node (ref "U3") (pin "9") (pinfunction "Q7S_9") (pintype "tri_state"))
    )
  )
)
